# sch_mcp2200.net
KiCad netlist of a schematic drawn in Altium Designer
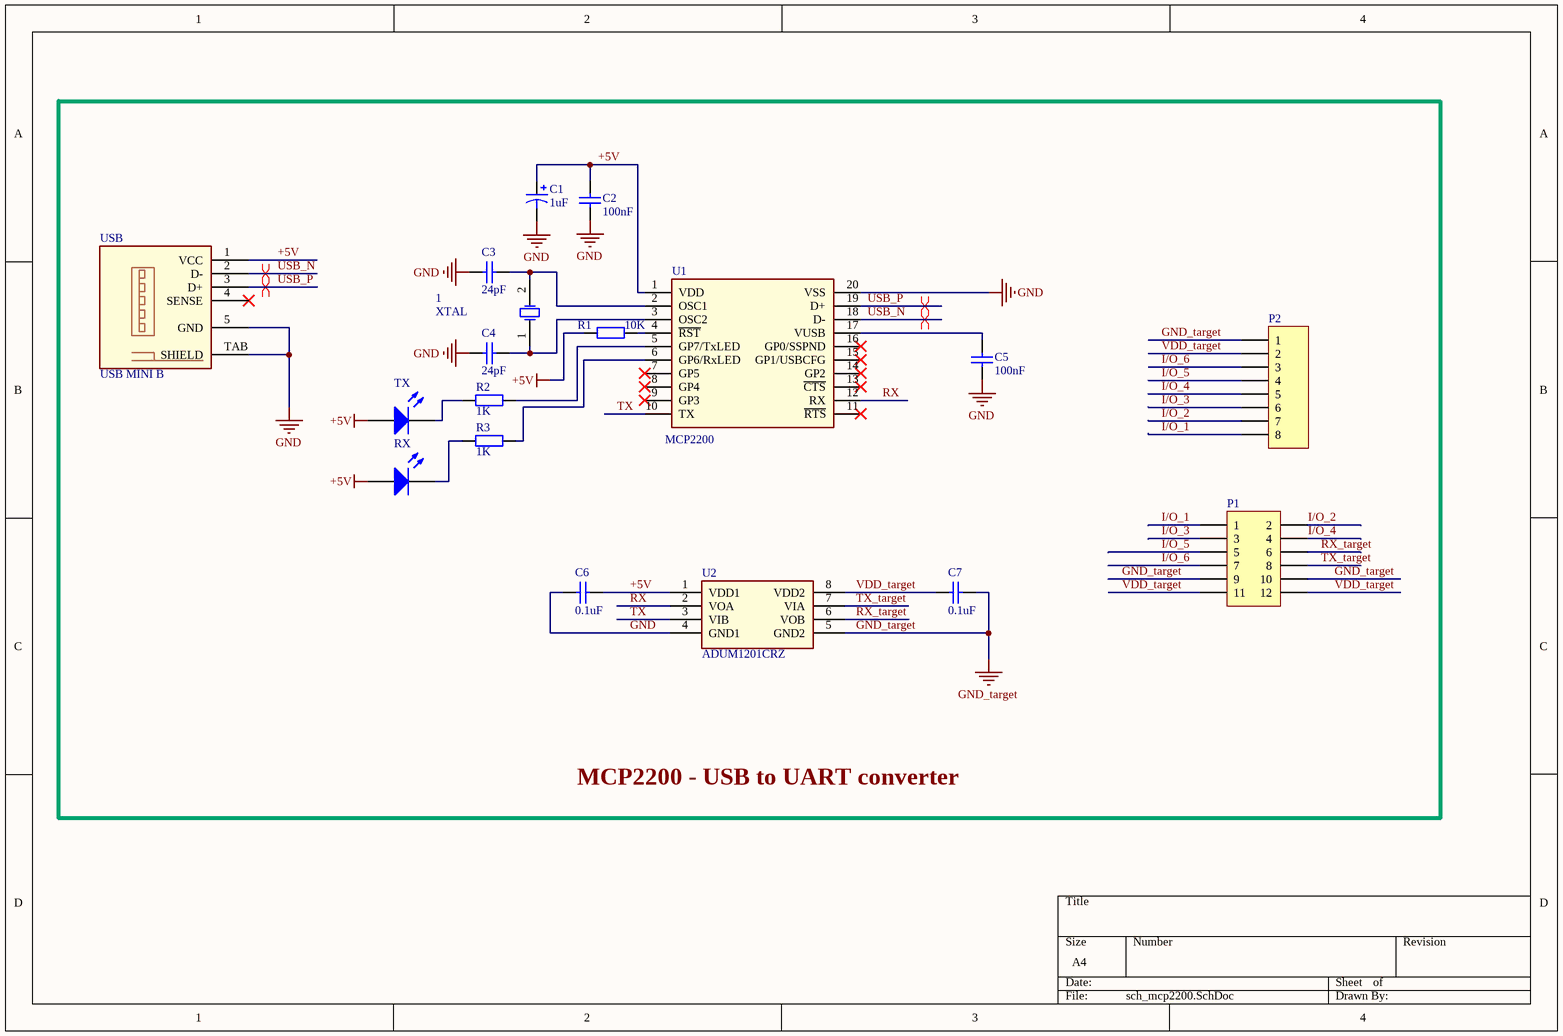
[diagram p0: sch_mcp2200.SchDoc]

(export (version "E")
  (design (tool "Eeschema 10.0.6"))
  (components
    (comp (ref "1")
      (value "XTAL")
      (footprint "Cuart_SMD_5032:Cuart_SMD_5032")
      (description "Crystal Oscillator")
      (fields (field (name "PUBLISHER") "Altium Limited"))
      (libsource (lib "Miscellaneous Devices") (part "XTAL"))
    )
    (comp (ref "C1")
      (value "1uF")
      (footprint "case A:case A")
      (description "Polarized Capacitor (Radial)")
      (fields (field (name "Comment") "Cap Pol1") (field (name "PUBLISHER") "Altium Limited"))
      (libsource (lib "Miscellaneous Devices") (part "Cap Pol1"))
    )
    (comp (ref "C2")
      (value "100nF")
      (footprint "0603 (C):0603(C)")
      (description "Capacitor")
      (fields (field (name "Comment") "Cap") (field (name "PUBLISHER") "Altium Limited"))
      (libsource (lib "Miscellaneous Devices") (part "Cap"))
    )
    (comp (ref "C3")
      (value "24pF")
      (footprint "0603 (C):0603(C)")
      (description "Capacitor")
      (fields (field (name "Comment") "Cap") (field (name "PUBLISHER") "Altium Limited"))
      (libsource (lib "Miscellaneous Devices") (part "Cap"))
    )
    (comp (ref "C4")
      (value "24pF")
      (footprint "0603 (C):0603(C)")
      (description "Capacitor")
      (fields (field (name "Comment") "Cap") (field (name "PUBLISHER") "Altium Limited"))
      (libsource (lib "Miscellaneous Devices") (part "Cap"))
    )
    (comp (ref "C5")
      (value "100nF")
      (footprint "0603 (C):0603(C)")
      (description "Capacitor")
      (fields (field (name "Comment") "Cap") (field (name "PUBLISHER") "Altium Limited"))
      (libsource (lib "Miscellaneous Devices") (part "Cap"))
    )
    (comp (ref "C6")
      (value "0.1uF")
      (footprint "0603 (C):0603(C)")
      (description "Capacitor")
      (fields (field (name "Comment") "Cap") (field (name "PUBLISHER") "Altium Limited"))
      (libsource (lib "Miscellaneous Devices") (part "Cap"))
    )
    (comp (ref "C7")
      (value "0.1uF")
      (footprint "0603 (C):0603(C)")
      (description "Capacitor")
      (fields (field (name "Comment") "Cap") (field (name "PUBLISHER") "Altium Limited"))
      (libsource (lib "Miscellaneous Devices") (part "Cap"))
    )
    (comp (ref "P1")
      (value "Header 6X2H")
      (footprint "Header 2x6_right angle:Header 2x6_right angle")
      (description "Header, 6-Pin, Dual row, Right Angle")
      (fields (field (name "PUBLISHER") "Altium Limited"))
      (libsource (lib "Miscellaneous Connectors") (part "Header 6X2H"))
    )
    (comp (ref "P2")
      (value "Header 8H")
      (footprint "Header_1x8_right angle:Header_1x8_right angle")
      (description "Header, 8-Pin, Right Angle")
      (fields (field (name "PUBLISHER") "Altium Limited"))
      (libsource (lib "Miscellaneous Connectors") (part "Header 8H"))
    )
    (comp (ref "R1")
      (value "10K")
      (footprint "Rezistor SMD(1608):RezistorSMD (1608)")
      (description "Resistor")
      (fields (field (name "Comment") "Res2") (field (name "PUBLISHER") "Altium Limited"))
      (libsource (lib "Miscellaneous Devices") (part "Res2"))
    )
    (comp (ref "R2")
      (value "1K")
      (footprint "Rezistor SMD(1608):RezistorSMD (1608)")
      (description "Resistor")
      (fields (field (name "Comment") "Res2") (field (name "PUBLISHER") "Altium Limited"))
      (libsource (lib "Miscellaneous Devices") (part "Res2"))
    )
    (comp (ref "R3")
      (value "1K")
      (footprint "Rezistor SMD(1608):RezistorSMD (1608)")
      (description "Resistor")
      (fields (field (name "Comment") "Res2") (field (name "PUBLISHER") "Altium Limited"))
      (libsource (lib "Miscellaneous Devices") (part "Res2"))
    )
    (comp (ref "RX")
      (value "LED3")
      (footprint "led smd verde:led smd verde")
      (description "Typical BLUE SiC LED")
      (fields (field (name "PUBLISHER") "Altium Limited"))
      (libsource (lib "Miscellaneous Devices") (part "LED3"))
    )
    (comp (ref "TX")
      (value "LED3")
      (footprint "led smd verde:led smd verde")
      (description "Typical BLUE SiC LED")
      (fields (field (name "PUBLISHER") "Altium Limited"))
      (libsource (lib "Miscellaneous Devices") (part "LED3"))
    )
    (comp (ref "U1")
      (value "MCP2200")
      (footprint "SOIC_20:SOIC_20")
      (description "USB 2.0 to UART Protocol Converter with GPIO")
      (libsource (lib "MCP2200") (part "MCP2200"))
    )
    (comp (ref "U2")
      (value "ADUM1201CRZ")
      (footprint "SOIC 8 pin:SOIC 8 pini")
      (libsource (lib "ADUM1201CRZ") (part "ADUM1201CRZ"))
    )
    (comp (ref "USB")
      (value "USB MINI B")
      (footprint "USB MINI B")
      (libsource (lib "USB B MINI") (part "USB MINI B"))
    )
  )
  (nets
    (net (code "1") (name "+5V") (class "Default")
      (node (ref "C1") (pin "1") (pinfunction "1_1") (pintype "passive"))
      (node (ref "C2") (pin "2") (pinfunction "2_2") (pintype "passive"))
      (node (ref "C6") (pin "2") (pinfunction "2_2") (pintype "passive"))
      (node (ref "R1") (pin "1") (pinfunction "1_1") (pintype "passive"))
      (node (ref "RX") (pin "1") (pinfunction "A_1") (pintype "passive"))
      (node (ref "TX") (pin "1") (pinfunction "A_1") (pintype "passive"))
      (node (ref "U1") (pin "1") (pinfunction "VDD_1") (pintype "passive"))
      (node (ref "U2") (pin "1") (pinfunction "VDD1_1") (pintype "passive"))
      (node (ref "USB") (pin "1") (pinfunction "VCC_1") (pintype "passive"))
    )
    (net (code "2") (name "/I{slash}O_1") (class "Default")
      (node (ref "P1") (pin "1") (pinfunction "1_1") (pintype "passive"))
      (node (ref "P2") (pin "8") (pinfunction "8_8") (pintype "passive"))
    )
    (net (code "3") (name "/I{slash}O_2") (class "Default")
      (node (ref "P1") (pin "2") (pinfunction "2_2") (pintype "passive"))
      (node (ref "P2") (pin "7") (pinfunction "7_7") (pintype "passive"))
    )
    (net (code "4") (name "/I{slash}O_3") (class "Default")
      (node (ref "P1") (pin "3") (pinfunction "3_3") (pintype "passive"))
      (node (ref "P2") (pin "6") (pinfunction "6_6") (pintype "passive"))
    )
    (net (code "5") (name "/I{slash}O_4") (class "Default")
      (node (ref "P1") (pin "4") (pinfunction "4_4") (pintype "passive"))
      (node (ref "P2") (pin "5") (pinfunction "5_5") (pintype "passive"))
    )
    (net (code "6") (name "/I{slash}O_5") (class "Default")
      (node (ref "P1") (pin "5") (pinfunction "5_5") (pintype "passive"))
      (node (ref "P2") (pin "4") (pinfunction "4_4") (pintype "passive"))
    )
    (net (code "7") (name "/I{slash}O_6") (class "Default")
      (node (ref "P1") (pin "7") (pinfunction "7_7") (pintype "passive"))
      (node (ref "P2") (pin "3") (pinfunction "3_3") (pintype "passive"))
    )
    (net (code "8") (name "/RX") (class "Default")
      (node (ref "U1") (pin "12") (pinfunction "RX_12") (pintype "passive"))
      (node (ref "U2") (pin "2") (pinfunction "VOA_2") (pintype "passive"))
    )
    (net (code "9") (name "/RX_target") (class "Default")
      (node (ref "P1") (pin "6") (pinfunction "6_6") (pintype "passive"))
      (node (ref "U2") (pin "6") (pinfunction "VOB_6") (pintype "passive"))
    )
    (net (code "10") (name "/TX") (class "Default")
      (node (ref "U1") (pin "10") (pinfunction "TX_10") (pintype "passive"))
      (node (ref "U2") (pin "3") (pinfunction "VIB_3") (pintype "passive"))
    )
    (net (code "11") (name "/TX_target") (class "Default")
      (node (ref "P1") (pin "8") (pinfunction "8_8") (pintype "passive"))
      (node (ref "U2") (pin "7") (pinfunction "VIA_7") (pintype "passive"))
    )
    (net (code "12") (name "/USB_N") (class "Default")
      (node (ref "U1") (pin "18") (pinfunction "D-_18") (pintype "passive"))
      (node (ref "USB") (pin "2") (pinfunction "D-_2") (pintype "passive"))
    )
    (net (code "13") (name "/USB_P") (class "Default")
      (node (ref "U1") (pin "19") (pinfunction "D+_19") (pintype "passive"))
      (node (ref "USB") (pin "3") (pinfunction "D+_3") (pintype "passive"))
    )
    (net (code "14") (name "/VDD_target") (class "Default")
      (node (ref "C7") (pin "1") (pinfunction "1_1") (pintype "passive"))
      (node (ref "P1") (pin "11") (pinfunction "11_11") (pintype "passive"))
      (node (ref "P1") (pin "12") (pinfunction "12_12") (pintype "passive"))
      (node (ref "P2") (pin "2") (pinfunction "2_2") (pintype "passive"))
      (node (ref "U2") (pin "8") (pinfunction "VDD2_8") (pintype "passive"))
    )
    (net (code "15") (name "GND") (class "Default")
      (node (ref "C1") (pin "2") (pinfunction "2_2") (pintype "passive"))
      (node (ref "C2") (pin "1") (pinfunction "1_1") (pintype "passive"))
      (node (ref "C3") (pin "2") (pinfunction "2_2") (pintype "passive"))
      (node (ref "C4") (pin "2") (pinfunction "2_2") (pintype "passive"))
      (node (ref "C5") (pin "1") (pinfunction "1_1") (pintype "passive"))
      (node (ref "C6") (pin "1") (pinfunction "1_1") (pintype "passive"))
      (node (ref "U1") (pin "20") (pinfunction "VSS_20") (pintype "passive"))
      (node (ref "U2") (pin "4") (pinfunction "GND1_4") (pintype "passive"))
      (node (ref "USB") (pin "5") (pinfunction "GND_5") (pintype "passive"))
      (node (ref "USB") (pin "TAB") (pinfunction "SHIELD_TAB") (pintype "passive"))
    )
    (net (code "16") (name "GND_target") (class "Default")
      (node (ref "C7") (pin "2") (pinfunction "2_2") (pintype "passive"))
      (node (ref "P1") (pin "10") (pinfunction "10_10") (pintype "passive"))
      (node (ref "P1") (pin "9") (pinfunction "9_9") (pintype "passive"))
      (node (ref "P2") (pin "1") (pinfunction "1_1") (pintype "passive"))
      (node (ref "U2") (pin "5") (pinfunction "GND2_5") (pintype "passive"))
    )
    (net (code "17") (name "Net-(1-OSC1)") (class "Default")
      (node (ref "1") (pin "1") (pinfunction "OSC1_1") (pintype "passive"))
      (node (ref "C4") (pin "1") (pinfunction "1_1") (pintype "passive"))
      (node (ref "U1") (pin "3") (pinfunction "OSC2_3") (pintype "passive"))
    )
    (net (code "18") (name "Net-(1-OSC2)") (class "Default")
      (node (ref "1") (pin "2") (pinfunction "OSC2_2") (pintype "passive"))
      (node (ref "C3") (pin "1") (pinfunction "1_1") (pintype "passive"))
      (node (ref "U1") (pin "2") (pinfunction "OSC1_2") (pintype "passive"))
    )
    (net (code "19") (name "Net-(RX-K)") (class "Default")
      (node (ref "R3") (pin "1") (pinfunction "1_1") (pintype "passive"))
      (node (ref "RX") (pin "2") (pinfunction "K_2") (pintype "passive"))
    )
    (net (code "20") (name "Net-(TX-K)") (class "Default")
      (node (ref "R2") (pin "1") (pinfunction "1_1") (pintype "passive"))
      (node (ref "TX") (pin "2") (pinfunction "K_2") (pintype "passive"))
    )
    (net (code "21") (name "Net-(U1-GP6{slash}RxLED)") (class "Default")
      (node (ref "R3") (pin "2") (pinfunction "2_2") (pintype "passive"))
      (node (ref "U1") (pin "6") (pinfunction "GP6/RxLED_6") (pintype "passive"))
    )
    (net (code "22") (name "Net-(U1-GP7{slash}TxLED)") (class "Default")
      (node (ref "R2") (pin "2") (pinfunction "2_2") (pintype "passive"))
      (node (ref "U1") (pin "5") (pinfunction "GP7/TxLED_5") (pintype "passive"))
    )
    (net (code "23") (name "Net-(U1-VUSB)") (class "Default")
      (node (ref "C5") (pin "2") (pinfunction "2_2") (pintype "passive"))
      (node (ref "U1") (pin "17") (pinfunction "VUSB_17") (pintype "passive"))
    )
    (net (code "24") (name "Net-(U1-~{RST})") (class "Default")
      (node (ref "R1") (pin "2") (pinfunction "2_2") (pintype "passive"))
      (node (ref "U1") (pin "4") (pinfunction "~{RST}_4") (pintype "passive"))
    )
    (net (code "25") (name "unconnected-(U1-GP0{slash}SSPND-Pad16)") (class "Default")
      (node (ref "U1") (pin "16") (pinfunction "GP0/SSPND_16") (pintype "passive+no_connect"))
    )
    (net (code "26") (name "unconnected-(U1-GP1{slash}USBCFG-Pad15)") (class "Default")
      (node (ref "U1") (pin "15") (pinfunction "GP1/USBCFG_15") (pintype "passive+no_connect"))
    )
    (net (code "27") (name "unconnected-(U1-GP2-Pad14)") (class "Default")
      (node (ref "U1") (pin "14") (pinfunction "GP2_14") (pintype "passive+no_connect"))
    )
    (net (code "28") (name "unconnected-(U1-GP3-Pad9)") (class "Default")
      (node (ref "U1") (pin "9") (pinfunction "GP3_9") (pintype "passive+no_connect"))
    )
    (net (code "29") (name "unconnected-(U1-GP4-Pad8)") (class "Default")
      (node (ref "U1") (pin "8") (pinfunction "GP4_8") (pintype "passive+no_connect"))
    )
    (net (code "30") (name "unconnected-(U1-GP5-Pad7)") (class "Default")
      (node (ref "U1") (pin "7") (pinfunction "GP5_7") (pintype "passive+no_connect"))
    )
    (net (code "31") (name "unconnected-(U1-~{CTS}-Pad13)") (class "Default")
      (node (ref "U1") (pin "13") (pinfunction "~{CTS}_13") (pintype "passive+no_connect"))
    )
    (net (code "32") (name "unconnected-(U1-~{RTS}-Pad11)") (class "Default")
      (node (ref "U1") (pin "11") (pinfunction "~{RTS}_11") (pintype "passive+no_connect"))
    )
    (net (code "33") (name "unconnected-(USB-SENSE-Pad4)") (class "Default")
      (node (ref "USB") (pin "4") (pinfunction "SENSE_4") (pintype "passive+no_connect"))
    )
  )
)
